# IOSection.net
KiCad netlist of a schematic drawn in Altium Designer
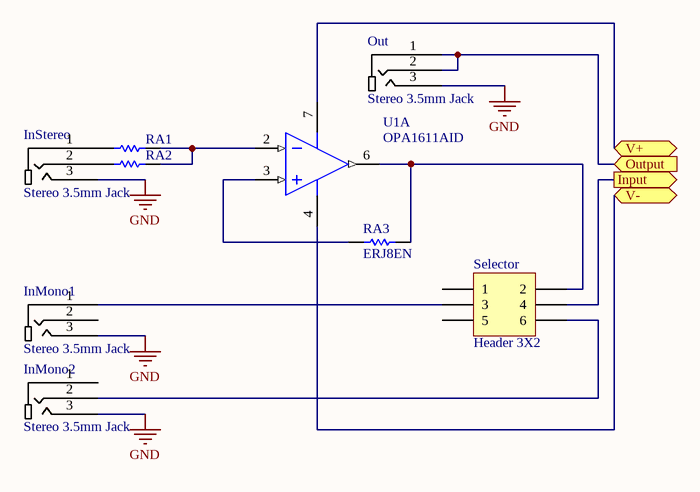
[diagram p0: IOSection.SchDoc]

(export (version "E")
  (design (tool "Eeschema 10.0.6"))
  (components
    (comp (ref "InMono1")
      (value "Stereo 3.5mm Jack")
      (footprint "3.5mm Audio Jack")
      (libsource (lib "Custom Parts") (part "Stereo 3.5mm Jack"))
    )
    (comp (ref "InMono2")
      (value "Stereo 3.5mm Jack")
      (footprint "3.5mm Audio Jack")
      (libsource (lib "Custom Parts") (part "Stereo 3.5mm Jack"))
    )
    (comp (ref "InStereo")
      (value "Stereo 3.5mm Jack")
      (footprint "3.5mm Audio Jack")
      (libsource (lib "Custom Parts") (part "Stereo 3.5mm Jack"))
    )
    (comp (ref "Out")
      (value "Stereo 3.5mm Jack")
      (footprint "3.5mm Audio Jack")
      (libsource (lib "Custom Parts") (part "Stereo 3.5mm Jack"))
    )
    (comp (ref "RA1")
      (value "ERJ8EN")
      (footprint "8-1206")
      (description "Precision Thick Film Chip Resistor, 10 Ohm to 2.2M Ohm Range, 1% Tolerance, 1206 Size, 0.125 W")
      (fields (field (name "PUBLISHER") "Altium Limited"))
      (libsource (lib "Panasonic Resistor") (part "ERJ8EN"))
    )
    (comp (ref "RA2")
      (value "ERJ8EN")
      (footprint "8-1206")
      (description "Precision Thick Film Chip Resistor, 10 Ohm to 2.2M Ohm Range, 1% Tolerance, 1206 Size, 0.125 W")
      (fields (field (name "PUBLISHER") "Altium Limited"))
      (libsource (lib "Panasonic Resistor") (part "ERJ8EN"))
    )
    (comp (ref "RA3")
      (value "ERJ8EN")
      (footprint "8-1206")
      (description "Precision Thick Film Chip Resistor, 10 Ohm to 2.2M Ohm Range, 1% Tolerance, 1206 Size, 0.125 W")
      (fields (field (name "PUBLISHER") "Altium Limited"))
      (libsource (lib "Panasonic Resistor") (part "ERJ8EN"))
    )
    (comp (ref "Selector")
      (value "Header 3X2")
      (footprint "HDR2X3")
      (description "Header, 3-Pin, Dual row")
      (fields (field (name "PUBLISHER") "Altium Limited"))
      (libsource (lib "Miscellaneous Connectors") (part "Header 3X2"))
    )
    (comp (ref "U1")
      (value "OPA1611AID")
      (footprint "TI-D8_N")
      (fields (field (name "MANUFACTURER") "Texas Instruments"))
      (libsource (lib "TI Amplifiers and Linear Operational Amplifier Audio Operational Amplifier") (part "OPA1611AID"))
    )
  )
  (nets
    (net (code "1") (name "/Input") (class "Default")
      (node (ref "Selector") (pin "4") (pinfunction "4_4") (pintype "passive"))
    )
    (net (code "2") (name "/Output") (class "Default")
      (node (ref "Out") (pin "1") (pinfunction "1_1") (pintype "passive"))
      (node (ref "Out") (pin "2") (pinfunction "2_2") (pintype "passive"))
    )
    (net (code "3") (name "/V+") (class "Default")
      (node (ref "U1") (pin "7") (pinfunction "V+_7") (pintype "power_in"))
    )
    (net (code "4") (name "/V-") (class "Default")
      (node (ref "U1") (pin "4") (pinfunction "V-_4") (pintype "power_in"))
    )
    (net (code "5") (name "GND") (class "Default")
      (node (ref "InMono1") (pin "3") (pinfunction "3_3") (pintype "passive"))
      (node (ref "InMono2") (pin "3") (pinfunction "3_3") (pintype "passive"))
      (node (ref "InStereo") (pin "3") (pinfunction "3_3") (pintype "passive"))
      (node (ref "Out") (pin "3") (pinfunction "3_3") (pintype "passive"))
    )
    (net (code "6") (name "Net-(InMono1-Pad1)") (class "Default")
      (node (ref "InMono1") (pin "1") (pinfunction "1_1") (pintype "passive"))
      (node (ref "Selector") (pin "3") (pinfunction "3_3") (pintype "passive"))
    )
    (net (code "7") (name "Net-(InMono2-Pad2)") (class "Default")
      (node (ref "InMono2") (pin "2") (pinfunction "2_2") (pintype "passive"))
      (node (ref "Selector") (pin "6") (pinfunction "6_6") (pintype "passive"))
    )
    (net (code "8") (name "Net-(InStereo-Pad1)") (class "Default")
      (node (ref "InStereo") (pin "1") (pinfunction "1_1") (pintype "passive"))
      (node (ref "RA1") (pin "1") (pinfunction "1_1") (pintype "passive"))
    )
    (net (code "9") (name "Net-(InStereo-Pad2)") (class "Default")
      (node (ref "InStereo") (pin "2") (pinfunction "2_2") (pintype "passive"))
      (node (ref "RA2") (pin "1") (pinfunction "1_1") (pintype "passive"))
    )
    (net (code "10") (name "Net-(U1A-IN+)") (class "Default")
      (node (ref "RA3") (pin "1") (pinfunction "1_1") (pintype "passive"))
      (node (ref "U1") (pin "3") (pinfunction "IN+_3") (pintype "input"))
    )
    (net (code "11") (name "Net-(U1A-IN-)") (class "Default")
      (node (ref "RA1") (pin "2") (pinfunction "2_2") (pintype "passive"))
      (node (ref "RA2") (pin "2") (pinfunction "2_2") (pintype "passive"))
      (node (ref "U1") (pin "2") (pinfunction "IN-_2") (pintype "input"))
    )
    (net (code "12") (name "Net-(U1A-OUT)") (class "Default")
      (node (ref "RA3") (pin "2") (pinfunction "2_2") (pintype "passive"))
      (node (ref "Selector") (pin "2") (pinfunction "2_2") (pintype "passive"))
      (node (ref "U1") (pin "6") (pinfunction "OUT_6") (pintype "output"))
    )
    (net (code "13") (name "unconnected-(InMono1-Pad2)") (class "Default")
      (node (ref "InMono1") (pin "2") (pinfunction "2_2") (pintype "passive"))
    )
    (net (code "14") (name "unconnected-(InMono2-Pad1)") (class "Default")
      (node (ref "InMono2") (pin "1") (pinfunction "1_1") (pintype "passive"))
    )
    (net (code "15") (name "unconnected-(Selector-Pad1)") (class "Default")
      (node (ref "Selector") (pin "1") (pinfunction "1_1") (pintype "passive"))
    )
    (net (code "16") (name "unconnected-(Selector-Pad5)") (class "Default")
      (node (ref "Selector") (pin "5") (pinfunction "5_5") (pintype "passive"))
    )
  )
)
